# uart.net
KiCad netlist of a schematic drawn in Altium Designer
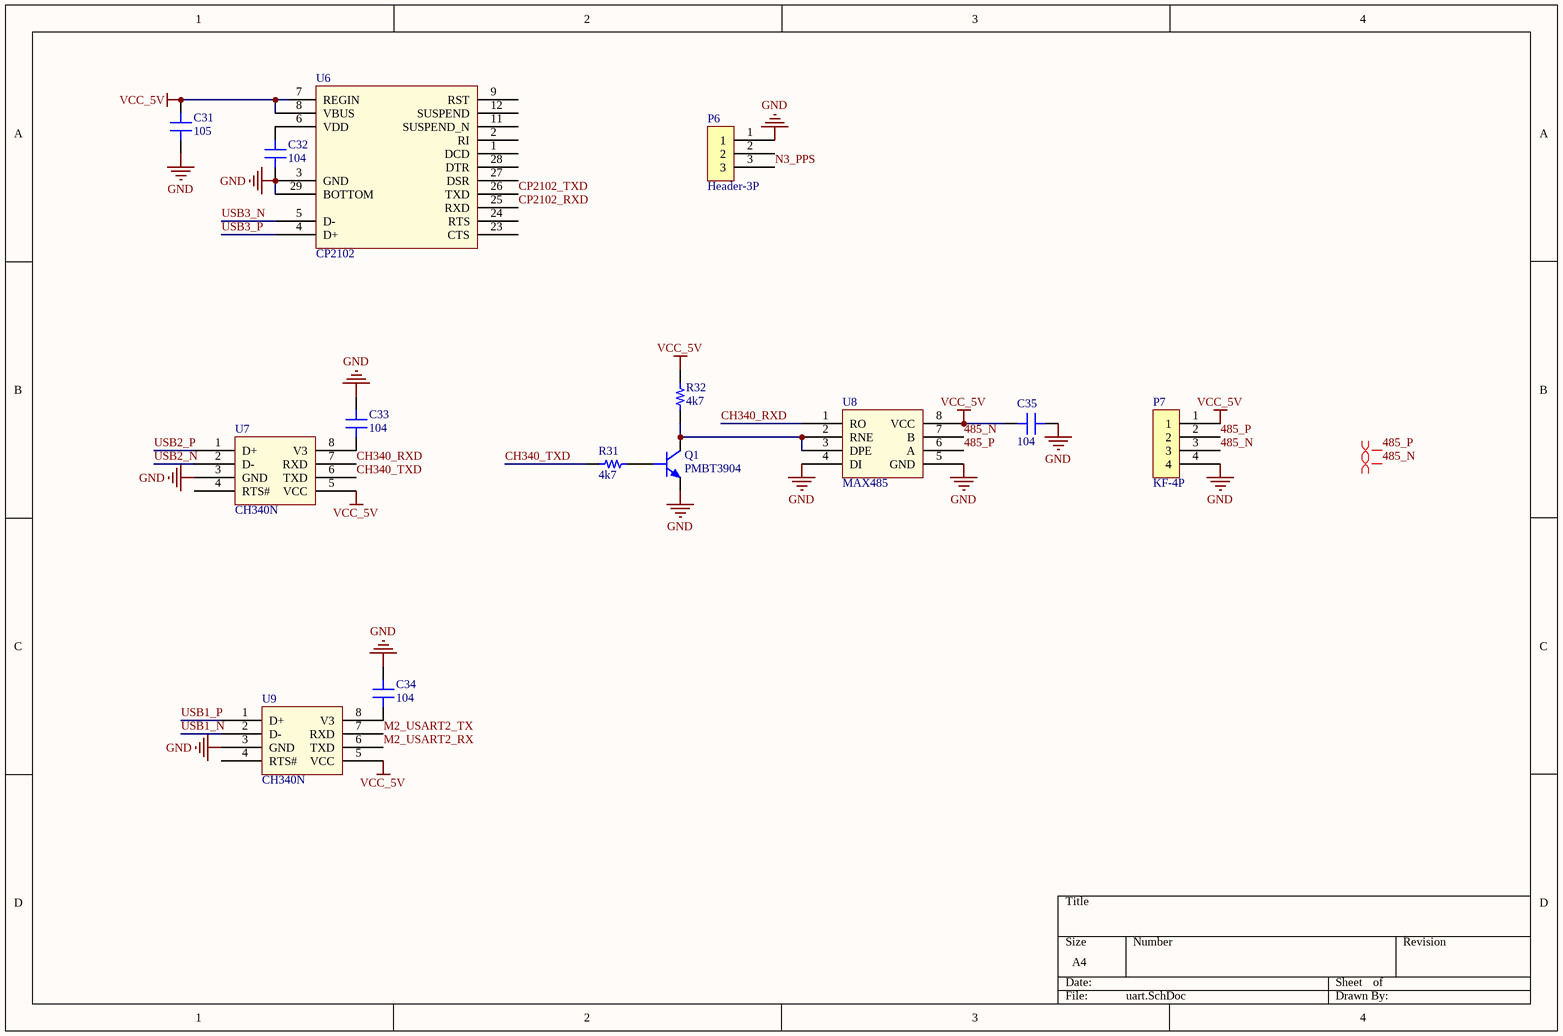
[diagram p0: uart.SchDoc]

(export (version "E")
  (design (tool "Eeschema 10.0.6"))
  (components
    (comp (ref "C31")
      (value "105")
      (footprint "C0603/1608")
      (description "陶瓷电容")
      (libsource (lib "WMJ2019_Devices") (part "陶瓷电容"))
    )
    (comp (ref "C32")
      (value "104")
      (footprint "C0603/1608")
      (description "陶瓷电容")
      (libsource (lib "WMJ2019_Devices") (part "陶瓷电容"))
    )
    (comp (ref "C33")
      (value "104")
      (footprint "C0603/1608")
      (description "陶瓷电容")
      (libsource (lib "WMJ2019_Devices") (part "陶瓷电容"))
    )
    (comp (ref "C34")
      (value "104")
      (footprint "C0603/1608")
      (description "陶瓷电容")
      (libsource (lib "WMJ2019_Devices") (part "陶瓷电容"))
    )
    (comp (ref "C35")
      (value "104")
      (footprint "C0603/1608")
      (description "陶瓷电容")
      (libsource (lib "WMJ2019_Devices") (part "陶瓷电容"))
    )
    (comp (ref "P6")
      (value "Header-3P")
      (footprint "HDR2.54-WI-3P")
      (libsource (lib "Connectors") (part "Header-3P"))
    )
    (comp (ref "P7")
      (value "KF-4P")
      (footprint "KF3.81-4P（卧式）")
      (libsource (lib "Connectors") (part "KF-4P"))
    )
    (comp (ref "Q1")
      (value "PMBT3904")
      (footprint "SOT-23-3")
      (description "NPN三极管")
      (fields (field (name "PUBLISHER") "Altium Limited"))
      (libsource (lib "Devices") (part "NPN"))
    )
    (comp (ref "R31")
      (value "4k7")
      (footprint "R0603/1608")
      (description "电阻")
      (libsource (lib "Devices") (part "电阻"))
    )
    (comp (ref "R32")
      (value "4k7")
      (footprint "R0603/1608")
      (description "电阻")
      (libsource (lib "Devices") (part "电阻"))
    )
    (comp (ref "U6")
      (value "CP2102")
      (footprint "QFN50P500X500-28VAM")
      (libsource (lib "Devices") (part "CP2102"))
    )
    (comp (ref "U7")
      (value "CH340N")
      (footprint "SOP-8")
      (description "USB-TTL转换芯片")
      (libsource (lib "Devices") (part "CH340N"))
    )
    (comp (ref "U8") (value "MAX485") (footprint "SOP-8") (libsource (lib "Devices") (part "MAX485")))
    (comp (ref "U9")
      (value "CH340N")
      (footprint "SOP-8")
      (description "USB-TTL转换芯片")
      (libsource (lib "Devices") (part "CH340N"))
    )
  )
  (nets
    (net (code "1") (name "/485_N") (class "Default")
      (node (ref "P7") (pin "3") (pinfunction "3_3") (pintype "passive"))
      (node (ref "U8") (pin "7") (pinfunction "B_7") (pintype "passive"))
    )
    (net (code "2") (name "/485_P") (class "Default")
      (node (ref "P7") (pin "2") (pinfunction "2_2") (pintype "passive"))
      (node (ref "U8") (pin "6") (pinfunction "A_6") (pintype "passive"))
    )
    (net (code "3") (name "/CH340_RXD") (class "Default")
      (node (ref "U7") (pin "7") (pinfunction "RXD_7") (pintype "passive"))
      (node (ref "U8") (pin "1") (pinfunction "RO_1") (pintype "passive"))
    )
    (net (code "4") (name "/CH340_TXD") (class "Default")
      (node (ref "R31") (pin "1") (pintype "passive"))
      (node (ref "U7") (pin "6") (pinfunction "TXD_6") (pintype "passive"))
    )
    (net (code "5") (name "/CP2102_RXD") (class "Default")
      (node (ref "U6") (pin "25") (pinfunction "RXD_25") (pintype "passive"))
    )
    (net (code "6") (name "/CP2102_TXD") (class "Default")
      (node (ref "U6") (pin "26") (pinfunction "TXD_26") (pintype "passive"))
    )
    (net (code "7") (name "/M2_USART2_RX") (class "Default")
      (node (ref "U9") (pin "6") (pinfunction "TXD_6") (pintype "passive"))
    )
    (net (code "8") (name "/M2_USART2_TX") (class "Default")
      (node (ref "U9") (pin "7") (pinfunction "RXD_7") (pintype "passive"))
    )
    (net (code "9") (name "/N3_PPS") (class "Default")
      (node (ref "P6") (pin "3") (pinfunction "3_3") (pintype "passive"))
    )
    (net (code "10") (name "/USB1_N") (class "Default")
      (node (ref "U9") (pin "2") (pinfunction "D-_2") (pintype "passive"))
    )
    (net (code "11") (name "/USB1_P") (class "Default")
      (node (ref "U9") (pin "1") (pinfunction "D+_1") (pintype "passive"))
    )
    (net (code "12") (name "/USB2_N") (class "Default")
      (node (ref "U7") (pin "2") (pinfunction "D-_2") (pintype "passive"))
    )
    (net (code "13") (name "/USB2_P") (class "Default")
      (node (ref "U7") (pin "1") (pinfunction "D+_1") (pintype "passive"))
    )
    (net (code "14") (name "/USB3_N") (class "Default")
      (node (ref "U6") (pin "5") (pinfunction "D-_5") (pintype "passive"))
    )
    (net (code "15") (name "/USB3_P") (class "Default")
      (node (ref "U6") (pin "4") (pinfunction "D+_4") (pintype "passive"))
    )
    (net (code "16") (name "GND") (class "Default")
      (node (ref "C31") (pin "1") (pintype "passive"))
      (node (ref "C32") (pin "1") (pintype "passive"))
      (node (ref "C33") (pin "2") (pintype "passive"))
      (node (ref "C34") (pin "2") (pintype "passive"))
      (node (ref "C35") (pin "1") (pintype "passive"))
      (node (ref "P6") (pin "1") (pinfunction "1_1") (pintype "passive"))
      (node (ref "P7") (pin "4") (pinfunction "4_4") (pintype "passive"))
      (node (ref "Q1") (pin "2") (pinfunction "E_2") (pintype "passive"))
      (node (ref "U6") (pin "29") (pinfunction "BOTTOM_29") (pintype "passive"))
      (node (ref "U6") (pin "3") (pinfunction "GND_3") (pintype "passive"))
      (node (ref "U7") (pin "3") (pinfunction "GND_3") (pintype "passive"))
      (node (ref "U8") (pin "4") (pinfunction "DI_4") (pintype "passive"))
      (node (ref "U8") (pin "5") (pinfunction "GND_5") (pintype "passive"))
      (node (ref "U9") (pin "3") (pinfunction "GND_3") (pintype "passive"))
    )
    (net (code "17") (name "Net-(Q1-B)") (class "Default")
      (node (ref "Q1") (pin "1") (pinfunction "B_1") (pintype "passive"))
      (node (ref "R31") (pin "2") (pintype "passive"))
    )
    (net (code "18") (name "Net-(Q1-C)") (class "Default")
      (node (ref "Q1") (pin "3") (pinfunction "C_3") (pintype "passive"))
      (node (ref "R32") (pin "2") (pintype "passive"))
      (node (ref "U8") (pin "2") (pinfunction "RNE_2") (pintype "passive"))
      (node (ref "U8") (pin "3") (pinfunction "DPE_3") (pintype "passive"))
    )
    (net (code "19") (name "Net-(U6-VDD)") (class "Default")
      (node (ref "C32") (pin "2") (pintype "passive"))
      (node (ref "U6") (pin "6") (pinfunction "VDD_6") (pintype "passive"))
    )
    (net (code "20") (name "Net-(U7-V3)") (class "Default")
      (node (ref "C33") (pin "1") (pintype "passive"))
      (node (ref "U7") (pin "8") (pinfunction "V3_8") (pintype "passive"))
    )
    (net (code "21") (name "Net-(U9-V3)") (class "Default")
      (node (ref "C34") (pin "1") (pintype "passive"))
      (node (ref "U9") (pin "8") (pinfunction "V3_8") (pintype "passive"))
    )
    (net (code "22") (name "VCC_5V") (class "Default")
      (node (ref "C31") (pin "2") (pintype "passive"))
      (node (ref "C35") (pin "2") (pintype "passive"))
      (node (ref "P7") (pin "1") (pinfunction "1_1") (pintype "passive"))
      (node (ref "R32") (pin "1") (pintype "passive"))
      (node (ref "U6") (pin "7") (pinfunction "REGIN_7") (pintype "passive"))
      (node (ref "U6") (pin "8") (pinfunction "VBUS_8") (pintype "passive"))
      (node (ref "U7") (pin "5") (pinfunction "VCC_5") (pintype "passive"))
      (node (ref "U8") (pin "8") (pinfunction "VCC_8") (pintype "passive"))
      (node (ref "U9") (pin "5") (pinfunction "VCC_5") (pintype "passive"))
    )
    (net (code "23") (name "unconnected-(P6-Pad2)") (class "Default")
      (node (ref "P6") (pin "2") (pinfunction "2_2") (pintype "passive"))
    )
    (net (code "24") (name "unconnected-(U6-CTS-Pad23)") (class "Default")
      (node (ref "U6") (pin "23") (pinfunction "CTS_23") (pintype "passive"))
    )
    (net (code "25") (name "unconnected-(U6-DCD-Pad1)") (class "Default")
      (node (ref "U6") (pin "1") (pinfunction "DCD_1") (pintype "passive"))
    )
    (net (code "26") (name "unconnected-(U6-DSR-Pad27)") (class "Default")
      (node (ref "U6") (pin "27") (pinfunction "DSR_27") (pintype "passive"))
    )
    (net (code "27") (name "unconnected-(U6-DTR-Pad28)") (class "Default")
      (node (ref "U6") (pin "28") (pinfunction "DTR_28") (pintype "passive"))
    )
    (net (code "28") (name "unconnected-(U6-RI-Pad2)") (class "Default")
      (node (ref "U6") (pin "2") (pinfunction "RI_2") (pintype "passive"))
    )
    (net (code "29") (name "unconnected-(U6-RST-Pad9)") (class "Default")
      (node (ref "U6") (pin "9") (pinfunction "RST_9") (pintype "passive"))
    )
    (net (code "30") (name "unconnected-(U6-RTS-Pad24)") (class "Default")
      (node (ref "U6") (pin "24") (pinfunction "RTS_24") (pintype "passive"))
    )
    (net (code "31") (name "unconnected-(U6-SUSPEND-Pad12)") (class "Default")
      (node (ref "U6") (pin "12") (pinfunction "SUSPEND_12") (pintype "passive"))
    )
    (net (code "32") (name "unconnected-(U6-SUSPEND_N-Pad11)") (class "Default")
      (node (ref "U6") (pin "11") (pinfunction "SUSPEND_N_11") (pintype "passive"))
    )
    (net (code "33") (name "unconnected-(U7-RTS#-Pad4)") (class "Default")
      (node (ref "U7") (pin "4") (pinfunction "RTS#_4") (pintype "passive"))
    )
    (net (code "34") (name "unconnected-(U9-RTS#-Pad4)") (class "Default")
      (node (ref "U9") (pin "4") (pinfunction "RTS#_4") (pintype "passive"))
    )
  )
)
